# Arduino_MEGA_home_HVAC_v2_0.net
KiCad netlist of a schematic drawn in EAGLE
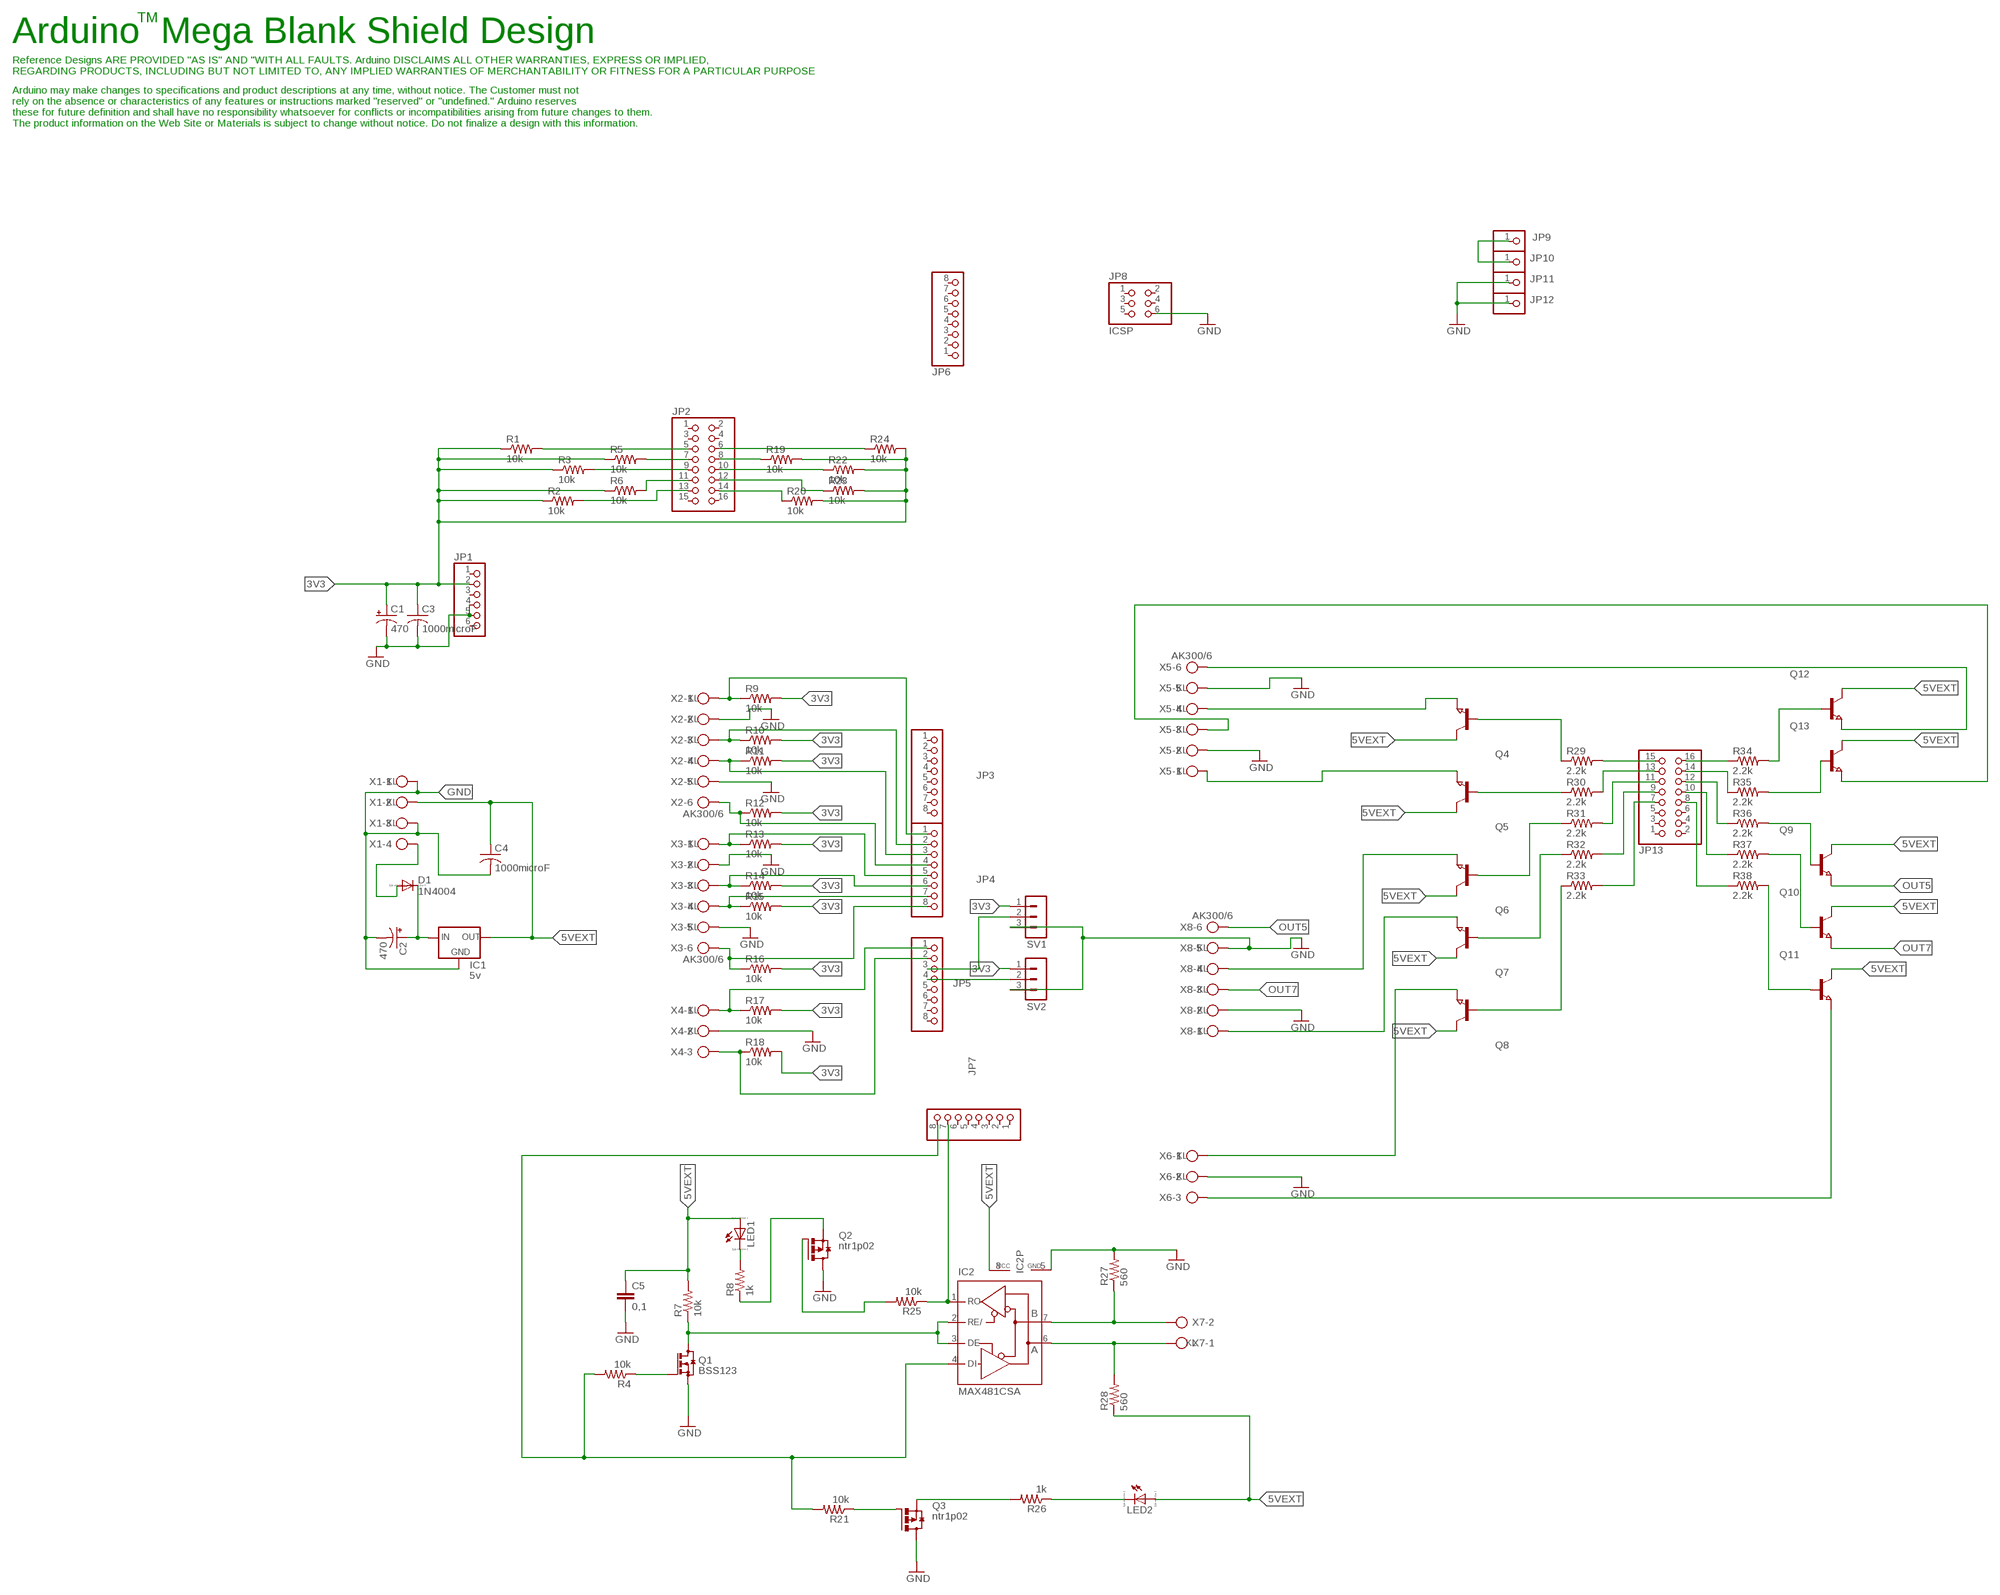
[diagram p0: schematic, sheet 1]

(export (version "E")
  (design (tool "Eeschema 10.0.6"))
  (components
    (comp (ref "C1")
      (value "470")
      (footprint "eagle-import:E5-6")
      (libsource (lib "eagle-import") (part "CPOL-USE5-6"))
    )
    (comp (ref "C2")
      (value "470")
      (footprint "eagle-import:E5-6")
      (libsource (lib "eagle-import") (part "CPOL-USE5-6"))
    )
    (comp (ref "C3")
      (value "1000microF")
      (footprint "eagle-import:C025-040X050")
      (libsource (lib "eagle-import") (part "C-US025-040X050"))
    )
    (comp (ref "C4")
      (value "1000microF")
      (footprint "eagle-import:C025-040X050")
      (libsource (lib "eagle-import") (part "C-US025-040X050"))
    )
    (comp (ref "C5")
      (value "0,1")
      (footprint "eagle-import:C2.5-2")
      (libsource (lib "eagle-import") (part "C2.5/2"))
    )
    (comp (ref "D1")
      (value "1N4004")
      (footprint "eagle-import:DO41-10")
      (libsource (lib "eagle-import") (part "1N4004"))
    )
    (comp (ref "IC1")
      (value "5v")
      (footprint "eagle-import:78MXXL")
      (libsource (lib "eagle-import") (part "78MXXL"))
    )
    (comp (ref "IC2")
      (value "MAX481CSA")
      (footprint "eagle-import:SO08")
      (fields (field (name "MF") "MAXIM"))
      (libsource (lib "eagle-import") (part "MAX481CSA"))
    )
    (comp (ref "JP1")
      (value "PINHD-1X6")
      (footprint "eagle-import:1X06")
      (libsource (lib "eagle-import") (part "PINHD-1X6"))
    )
    (comp (ref "JP2")
      (value "PINHD-2X8")
      (footprint "eagle-import:2X08")
      (libsource (lib "eagle-import") (part "PINHD-2X8"))
    )
    (comp (ref "JP3")
      (value "PINHD-1X8")
      (footprint "eagle-import:1X08")
      (libsource (lib "eagle-import") (part "PINHD-1X8"))
    )
    (comp (ref "JP4")
      (value "PINHD-1X8")
      (footprint "eagle-import:1X08")
      (libsource (lib "eagle-import") (part "PINHD-1X8"))
    )
    (comp (ref "JP5")
      (value "PINHD-1X8")
      (footprint "eagle-import:1X08")
      (libsource (lib "eagle-import") (part "PINHD-1X8"))
    )
    (comp (ref "JP6")
      (value "PINHD-1X8")
      (footprint "eagle-import:1X08")
      (libsource (lib "eagle-import") (part "PINHD-1X8"))
    )
    (comp (ref "JP7")
      (value "PINHD-1X8")
      (footprint "eagle-import:1X08")
      (libsource (lib "eagle-import") (part "PINHD-1X8"))
    )
    (comp (ref "JP8")
      (value "ICSP")
      (footprint "eagle-import:2X03")
      (libsource (lib "eagle-import") (part "PINHD-2X3"))
    )
    (comp (ref "JP9")
      (value "PINHD-1X1")
      (footprint "eagle-import:1X01")
      (libsource (lib "eagle-import") (part "PINHD-1X1"))
    )
    (comp (ref "JP10")
      (value "PINHD-1X1")
      (footprint "eagle-import:1X01")
      (libsource (lib "eagle-import") (part "PINHD-1X1"))
    )
    (comp (ref "JP11")
      (value "PINHD-1X1")
      (footprint "eagle-import:1X01")
      (libsource (lib "eagle-import") (part "PINHD-1X1"))
    )
    (comp (ref "JP12")
      (value "PINHD-1X1")
      (footprint "eagle-import:1X01")
      (libsource (lib "eagle-import") (part "PINHD-1X1"))
    )
    (comp (ref "JP13")
      (value "PINHD-2X8")
      (footprint "eagle-import:2X08")
      (libsource (lib "eagle-import") (part "PINHD-2X8"))
    )
    (comp (ref "LED1")
      (value "LED_E")
      (footprint "eagle-import:LED_1206")
      (libsource (lib "eagle-import") (part "LED_E"))
    )
    (comp (ref "LED2")
      (value "LED_E")
      (footprint "eagle-import:LED_1206")
      (libsource (lib "eagle-import") (part "LED_E"))
    )
    (comp (ref "Q1")
      (value "BSS123")
      (footprint "eagle-import:SOT23")
      (libsource (lib "eagle-import") (part "BSS123"))
    )
    (comp (ref "Q2")
      (value "ntr1p02")
      (footprint "eagle-import:SUPER-SOT3")
      (libsource (lib "eagle-import") (part "FDN360P"))
    )
    (comp (ref "Q3")
      (value "ntr1p02")
      (footprint "eagle-import:SUPER-SOT3")
      (libsource (lib "eagle-import") (part "FDN360P"))
    )
    (comp (ref "Q4")
      (value "NPN-TRANSISTOR_SOT23")
      (footprint "eagle-import:SOT23")
      (libsource (lib "eagle-import") (part "NPN-TRANSISTOR_SOT23"))
    )
    (comp (ref "Q5")
      (value "NPN-TRANSISTOR_SOT23")
      (footprint "eagle-import:SOT23")
      (libsource (lib "eagle-import") (part "NPN-TRANSISTOR_SOT23"))
    )
    (comp (ref "Q6")
      (value "NPN-TRANSISTOR_SOT23")
      (footprint "eagle-import:SOT23")
      (libsource (lib "eagle-import") (part "NPN-TRANSISTOR_SOT23"))
    )
    (comp (ref "Q7")
      (value "NPN-TRANSISTOR_SOT23")
      (footprint "eagle-import:SOT23")
      (libsource (lib "eagle-import") (part "NPN-TRANSISTOR_SOT23"))
    )
    (comp (ref "Q8")
      (value "NPN-TRANSISTOR_SOT23")
      (footprint "eagle-import:SOT23")
      (libsource (lib "eagle-import") (part "NPN-TRANSISTOR_SOT23"))
    )
    (comp (ref "Q9")
      (value "NPN-TRANSISTOR_SOT23")
      (footprint "eagle-import:SOT23")
      (libsource (lib "eagle-import") (part "NPN-TRANSISTOR_SOT23"))
    )
    (comp (ref "Q10")
      (value "NPN-TRANSISTOR_SOT23")
      (footprint "eagle-import:SOT23")
      (libsource (lib "eagle-import") (part "NPN-TRANSISTOR_SOT23"))
    )
    (comp (ref "Q11")
      (value "NPN-TRANSISTOR_SOT23")
      (footprint "eagle-import:SOT23")
      (libsource (lib "eagle-import") (part "NPN-TRANSISTOR_SOT23"))
    )
    (comp (ref "Q12")
      (value "NPN-TRANSISTOR_SOT23")
      (footprint "eagle-import:SOT23")
      (libsource (lib "eagle-import") (part "NPN-TRANSISTOR_SOT23"))
    )
    (comp (ref "Q13")
      (value "NPN-TRANSISTOR_SOT23")
      (footprint "eagle-import:SOT23")
      (libsource (lib "eagle-import") (part "NPN-TRANSISTOR_SOT23"))
    )
    (comp (ref "R1")
      (value "10k")
      (footprint "eagle-import:R0805")
      (libsource (lib "eagle-import") (part "R-US_R0805"))
    )
    (comp (ref "R2")
      (value "10k")
      (footprint "eagle-import:R0805")
      (libsource (lib "eagle-import") (part "R-US_R0805"))
    )
    (comp (ref "R3")
      (value "10k")
      (footprint "eagle-import:R0805")
      (libsource (lib "eagle-import") (part "R-US_R0805"))
    )
    (comp (ref "R4")
      (value "10k")
      (footprint "eagle-import:R0805")
      (libsource (lib "eagle-import") (part "R-US_R0805"))
    )
    (comp (ref "R5")
      (value "10k")
      (footprint "eagle-import:R0805")
      (libsource (lib "eagle-import") (part "R-US_R0805"))
    )
    (comp (ref "R6")
      (value "10k")
      (footprint "eagle-import:R0805")
      (libsource (lib "eagle-import") (part "R-US_R0805"))
    )
    (comp (ref "R7")
      (value "10k")
      (footprint "eagle-import:R0805")
      (libsource (lib "eagle-import") (part "R-US_R0805"))
    )
    (comp (ref "R8")
      (value "1k")
      (footprint "eagle-import:R0805")
      (libsource (lib "eagle-import") (part "R-US_R0805"))
    )
    (comp (ref "R9")
      (value "10k")
      (footprint "eagle-import:R0805")
      (libsource (lib "eagle-import") (part "R-US_R0805"))
    )
    (comp (ref "R10")
      (value "10k")
      (footprint "eagle-import:R0805")
      (libsource (lib "eagle-import") (part "R-US_R0805"))
    )
    (comp (ref "R11")
      (value "10k")
      (footprint "eagle-import:R0805")
      (libsource (lib "eagle-import") (part "R-US_R0805"))
    )
    (comp (ref "R12")
      (value "10k")
      (footprint "eagle-import:R0805")
      (libsource (lib "eagle-import") (part "R-US_R0805"))
    )
    (comp (ref "R13")
      (value "10k")
      (footprint "eagle-import:R0805")
      (libsource (lib "eagle-import") (part "R-US_R0805"))
    )
    (comp (ref "R14")
      (value "10k")
      (footprint "eagle-import:R0805")
      (libsource (lib "eagle-import") (part "R-US_R0805"))
    )
    (comp (ref "R15")
      (value "10k")
      (footprint "eagle-import:R0805")
      (libsource (lib "eagle-import") (part "R-US_R0805"))
    )
    (comp (ref "R16")
      (value "10k")
      (footprint "eagle-import:R0805")
      (libsource (lib "eagle-import") (part "R-US_R0805"))
    )
    (comp (ref "R17")
      (value "10k")
      (footprint "eagle-import:R0805")
      (libsource (lib "eagle-import") (part "R-US_R0805"))
    )
    (comp (ref "R18")
      (value "10k")
      (footprint "eagle-import:R0805")
      (libsource (lib "eagle-import") (part "R-US_R0805"))
    )
    (comp (ref "R19")
      (value "10k")
      (footprint "eagle-import:R0805")
      (libsource (lib "eagle-import") (part "R-US_R0805"))
    )
    (comp (ref "R20")
      (value "10k")
      (footprint "eagle-import:R0805")
      (libsource (lib "eagle-import") (part "R-US_R0805"))
    )
    (comp (ref "R21")
      (value "10k")
      (footprint "eagle-import:R0805")
      (libsource (lib "eagle-import") (part "R-US_R0805"))
    )
    (comp (ref "R22")
      (value "10k")
      (footprint "eagle-import:R0805")
      (libsource (lib "eagle-import") (part "R-US_R0805"))
    )
    (comp (ref "R23")
      (value "10k")
      (footprint "eagle-import:R0805")
      (libsource (lib "eagle-import") (part "R-US_R0805"))
    )
    (comp (ref "R24")
      (value "10k")
      (footprint "eagle-import:R0805")
      (libsource (lib "eagle-import") (part "R-US_R0805"))
    )
    (comp (ref "R25")
      (value "10k")
      (footprint "eagle-import:R0805")
      (libsource (lib "eagle-import") (part "R-US_R0805"))
    )
    (comp (ref "R26")
      (value "1k")
      (footprint "eagle-import:R0805")
      (libsource (lib "eagle-import") (part "R-US_R0805"))
    )
    (comp (ref "R27")
      (value "560")
      (footprint "eagle-import:R0805")
      (libsource (lib "eagle-import") (part "R-US_R0805"))
    )
    (comp (ref "R28")
      (value "560")
      (footprint "eagle-import:R0805")
      (libsource (lib "eagle-import") (part "R-US_R0805"))
    )
    (comp (ref "R29")
      (value "2.2k")
      (footprint "eagle-import:M0805")
      (libsource (lib "eagle-import") (part "R-US_M0805"))
    )
    (comp (ref "R30")
      (value "2.2k")
      (footprint "eagle-import:M0805")
      (libsource (lib "eagle-import") (part "R-US_M0805"))
    )
    (comp (ref "R31")
      (value "2.2k")
      (footprint "eagle-import:M0805")
      (libsource (lib "eagle-import") (part "R-US_M0805"))
    )
    (comp (ref "R32")
      (value "2.2k")
      (footprint "eagle-import:M0805")
      (libsource (lib "eagle-import") (part "R-US_M0805"))
    )
    (comp (ref "R33")
      (value "2.2k")
      (footprint "eagle-import:M0805")
      (libsource (lib "eagle-import") (part "R-US_M0805"))
    )
    (comp (ref "R34")
      (value "2.2k")
      (footprint "eagle-import:M0805")
      (libsource (lib "eagle-import") (part "R-US_M0805"))
    )
    (comp (ref "R35")
      (value "2.2k")
      (footprint "eagle-import:M0805")
      (libsource (lib "eagle-import") (part "R-US_M0805"))
    )
    (comp (ref "R36")
      (value "2.2k")
      (footprint "eagle-import:M0805")
      (libsource (lib "eagle-import") (part "R-US_M0805"))
    )
    (comp (ref "R37")
      (value "2.2k")
      (footprint "eagle-import:M0805")
      (libsource (lib "eagle-import") (part "R-US_M0805"))
    )
    (comp (ref "R38")
      (value "2.2k")
      (footprint "eagle-import:M0805")
      (libsource (lib "eagle-import") (part "R-US_M0805"))
    )
    (comp (ref "SV1")
      (value "MA03-1")
      (footprint "eagle-import:MA03-1")
      (libsource (lib "eagle-import") (part "MA03-1"))
    )
    (comp (ref "SV2")
      (value "MA03-1")
      (footprint "eagle-import:MA03-1")
      (libsource (lib "eagle-import") (part "MA03-1"))
    )
    (comp (ref "X1")
      (value "AK500/4")
      (footprint "eagle-import:AK500_4")
      (libsource (lib "eagle-import") (part "AK500/4"))
    )
    (comp (ref "X2")
      (value "AK300/6")
      (footprint "eagle-import:AK300_6")
      (libsource (lib "eagle-import") (part "AK300/6"))
    )
    (comp (ref "X3")
      (value "AK300/6")
      (footprint "eagle-import:AK300_6")
      (libsource (lib "eagle-import") (part "AK300/6"))
    )
    (comp (ref "X4")
      (value "AK300/3")
      (footprint "eagle-import:AK300_3")
      (libsource (lib "eagle-import") (part "AK300/3"))
    )
    (comp (ref "X5")
      (value "AK300/6")
      (footprint "eagle-import:AK300_6")
      (libsource (lib "eagle-import") (part "AK300/6"))
    )
    (comp (ref "X6")
      (value "AK300/3")
      (footprint "eagle-import:AK300_3")
      (libsource (lib "eagle-import") (part "AK300/3"))
    )
    (comp (ref "X7")
      (value "AK300/2")
      (footprint "eagle-import:AK300_2")
      (libsource (lib "eagle-import") (part "AK300/2"))
    )
    (comp (ref "X8")
      (value "AK300/6")
      (footprint "eagle-import:AK300_6")
      (libsource (lib "eagle-import") (part "AK300/6"))
    )
  )
  (nets
    (net (code "1") (name "3V3") (class "Default")
      (node (ref "C1") (pin "+") (pinfunction "+_+") (pintype "passive"))
      (node (ref "C3") (pin "1") (pinfunction "1_1") (pintype "passive"))
      (node (ref "JP1") (pin "2") (pinfunction "2_2") (pintype "passive"))
      (node (ref "R1") (pin "1") (pinfunction "1_1") (pintype "passive"))
      (node (ref "R10") (pin "2") (pinfunction "2_2") (pintype "passive"))
      (node (ref "R11") (pin "2") (pinfunction "2_2") (pintype "passive"))
      (node (ref "R12") (pin "2") (pinfunction "2_2") (pintype "passive"))
      (node (ref "R13") (pin "2") (pinfunction "2_2") (pintype "passive"))
      (node (ref "R14") (pin "2") (pinfunction "2_2") (pintype "passive"))
      (node (ref "R15") (pin "2") (pinfunction "2_2") (pintype "passive"))
      (node (ref "R16") (pin "2") (pinfunction "2_2") (pintype "passive"))
      (node (ref "R17") (pin "2") (pinfunction "2_2") (pintype "passive"))
      (node (ref "R18") (pin "2") (pinfunction "2_2") (pintype "passive"))
      (node (ref "R19") (pin "2") (pinfunction "2_2") (pintype "passive"))
      (node (ref "R2") (pin "1") (pinfunction "1_1") (pintype "passive"))
      (node (ref "R20") (pin "2") (pinfunction "2_2") (pintype "passive"))
      (node (ref "R22") (pin "2") (pinfunction "2_2") (pintype "passive"))
      (node (ref "R23") (pin "2") (pinfunction "2_2") (pintype "passive"))
      (node (ref "R24") (pin "2") (pinfunction "2_2") (pintype "passive"))
      (node (ref "R3") (pin "1") (pinfunction "1_1") (pintype "passive"))
      (node (ref "R5") (pin "1") (pinfunction "1_1") (pintype "passive"))
      (node (ref "R6") (pin "1") (pinfunction "1_1") (pintype "passive"))
      (node (ref "R9") (pin "2") (pinfunction "2_2") (pintype "passive"))
      (node (ref "SV1") (pin "1") (pinfunction "1_1") (pintype "passive"))
      (node (ref "SV2") (pin "1") (pinfunction "1_1") (pintype "passive"))
    )
    (net (code "2") (name "5VEXT") (class "Default")
      (node (ref "C4") (pin "1") (pinfunction "1_1") (pintype "passive"))
      (node (ref "C5") (pin "1") (pinfunction "1_1") (pintype "passive"))
      (node (ref "IC1") (pin "OUT") (pinfunction "OUT_OUT") (pintype "passive"))
      (node (ref "IC2") (pin "8") (pinfunction "VCC_8") (pintype "power_in"))
      (node (ref "LED1") (pin "A") (pinfunction "A_A") (pintype "passive"))
      (node (ref "LED2") (pin "A") (pinfunction "A_A") (pintype "passive"))
      (node (ref "Q10") (pin "3") (pinfunction "C_3") (pintype "passive"))
      (node (ref "Q11") (pin "3") (pinfunction "C_3") (pintype "passive"))
      (node (ref "Q12") (pin "3") (pinfunction "C_3") (pintype "passive"))
      (node (ref "Q13") (pin "3") (pinfunction "C_3") (pintype "passive"))
      (node (ref "Q4") (pin "3") (pinfunction "C_3") (pintype "passive"))
      (node (ref "Q5") (pin "3") (pinfunction "C_3") (pintype "passive"))
      (node (ref "Q6") (pin "3") (pinfunction "C_3") (pintype "passive"))
      (node (ref "Q7") (pin "3") (pinfunction "C_3") (pintype "passive"))
      (node (ref "Q8") (pin "3") (pinfunction "C_3") (pintype "passive"))
      (node (ref "Q9") (pin "3") (pinfunction "C_3") (pintype "passive"))
      (node (ref "R28") (pin "1") (pinfunction "1_1") (pintype "passive"))
      (node (ref "R7") (pin "2") (pinfunction "2_2") (pintype "passive"))
      (node (ref "X1") (pin "2") (pinfunction "KL_2") (pintype "passive"))
    )
    (net (code "3") (name "GND") (class "Default")
      (node (ref "C1") (pin "-") (pinfunction "-_-") (pintype "passive"))
      (node (ref "C2") (pin "-") (pinfunction "-_-") (pintype "passive"))
      (node (ref "C3") (pin "2") (pinfunction "2_2") (pintype "passive"))
      (node (ref "C4") (pin "2") (pinfunction "2_2") (pintype "passive"))
      (node (ref "C5") (pin "2") (pinfunction "2_2") (pintype "passive"))
      (node (ref "IC1") (pin "GND") (pinfunction "GND_GND") (pintype "input"))
      (node (ref "IC2") (pin "5") (pinfunction "GND_5") (pintype "power_in"))
      (node (ref "JP1") (pin "4") (pinfunction "4_4") (pintype "passive"))
      (node (ref "JP1") (pin "5") (pinfunction "5_5") (pintype "passive"))
      (node (ref "JP11") (pin "1") (pinfunction "1_1") (pintype "passive"))
      (node (ref "JP12") (pin "1") (pinfunction "1_1") (pintype "passive"))
      (node (ref "JP8") (pin "6") (pinfunction "6_6") (pintype "passive"))
      (node (ref "Q1") (pin "2") (pinfunction "S_2") (pintype "passive"))
      (node (ref "Q2") (pin "3") (pinfunction "D_3") (pintype "passive"))
      (node (ref "Q3") (pin "3") (pinfunction "D_3") (pintype "passive"))
      (node (ref "R27") (pin "2") (pinfunction "2_2") (pintype "passive"))
      (node (ref "SV1") (pin "3") (pinfunction "3_3") (pintype "passive"))
      (node (ref "SV2") (pin "3") (pinfunction "3_3") (pintype "passive"))
      (node (ref "X1") (pin "1") (pinfunction "KL_1") (pintype "passive"))
      (node (ref "X1") (pin "3") (pinfunction "KL_3") (pintype "passive"))
      (node (ref "X2") (pin "2") (pinfunction "KL_2") (pintype "passive"))
      (node (ref "X2") (pin "5") (pinfunction "KL_5") (pintype "passive"))
      (node (ref "X3") (pin "2") (pinfunction "KL_2") (pintype "passive"))
      (node (ref "X3") (pin "5") (pinfunction "KL_5") (pintype "passive"))
      (node (ref "X4") (pin "2") (pinfunction "KL_2") (pintype "passive"))
      (node (ref "X5") (pin "2") (pinfunction "KL_2") (pintype "passive"))
      (node (ref "X5") (pin "5") (pinfunction "KL_5") (pintype "passive"))
      (node (ref "X6") (pin "2") (pinfunction "KL_2") (pintype "passive"))
      (node (ref "X8") (pin "2") (pinfunction "KL_2") (pintype "passive"))
      (node (ref "X8") (pin "5") (pinfunction "KL_5") (pintype "passive"))
    )
    (net (code "4") (name "Net-(C2-Pad+)") (class "Default")
      (node (ref "C2") (pin "+") (pinfunction "+_+") (pintype "passive"))
      (node (ref "D1") (pin "C") (pinfunction "C_C") (pintype "passive"))
      (node (ref "IC1") (pin "IN") (pinfunction "IN_IN") (pintype "input"))
    )
    (net (code "5") (name "Net-(IC2A-A)") (class "Default")
      (node (ref "IC2") (pin "6") (pinfunction "A_6") (pintype "passive"))
      (node (ref "R28") (pin "2") (pinfunction "2_2") (pintype "passive"))
      (node (ref "X7") (pin "1") (pinfunction "KL_1") (pintype "passive"))
    )
    (net (code "6") (name "Net-(IC2A-B)") (class "Default")
      (node (ref "IC2") (pin "7") (pinfunction "B_7") (pintype "passive"))
      (node (ref "R27") (pin "1") (pinfunction "1_1") (pintype "passive"))
      (node (ref "X7") (pin "2") (pinfunction "KL_2") (pintype "passive"))
    )
    (net (code "7") (name "Net-(IC2A-DE)") (class "Default")
      (node (ref "IC2") (pin "2") (pinfunction "RE/_2") (pintype "input"))
      (node (ref "IC2") (pin "3") (pinfunction "DE_3") (pintype "input"))
      (node (ref "Q1") (pin "3") (pinfunction "D_3") (pintype "passive"))
      (node (ref "R7") (pin "1") (pinfunction "1_1") (pintype "passive"))
    )
    (net (code "8") (name "Net-(IC2A-DI)") (class "Default")
      (node (ref "IC2") (pin "4") (pinfunction "DI_4") (pintype "input"))
      (node (ref "JP7") (pin "8") (pinfunction "8_8") (pintype "passive"))
      (node (ref "R21") (pin "2") (pinfunction "2_2") (pintype "passive"))
      (node (ref "R4") (pin "2") (pinfunction "2_2") (pintype "passive"))
    )
    (net (code "9") (name "Net-(IC2A-RO)") (class "Default")
      (node (ref "IC2") (pin "1") (pinfunction "RO_1") (pintype "output"))
      (node (ref "JP7") (pin "7") (pinfunction "7_7") (pintype "passive"))
      (node (ref "R25") (pin "1") (pinfunction "1_1") (pintype "passive"))
    )
    (net (code "10") (name "Net-(JP2-Pad5)") (class "Default")
      (node (ref "JP2") (pin "5") (pinfunction "5_5") (pintype "passive"))
      (node (ref "R1") (pin "2") (pinfunction "2_2") (pintype "passive"))
    )
    (net (code "11") (name "Net-(JP2-Pad6)") (class "Default")
      (node (ref "JP2") (pin "6") (pinfunction "6_6") (pintype "passive"))
      (node (ref "R24") (pin "1") (pinfunction "1_1") (pintype "passive"))
    )
    (net (code "12") (name "Net-(JP2-Pad7)") (class "Default")
      (node (ref "JP2") (pin "7") (pinfunction "7_7") (pintype "passive"))
      (node (ref "R5") (pin "2") (pinfunction "2_2") (pintype "passive"))
    )
    (net (code "13") (name "Net-(JP2-Pad8)") (class "Default")
      (node (ref "JP2") (pin "8") (pinfunction "8_8") (pintype "passive"))
      (node (ref "R19") (pin "1") (pinfunction "1_1") (pintype "passive"))
    )
    (net (code "14") (name "Net-(JP2-Pad9)") (class "Default")
      (node (ref "JP2") (pin "9") (pinfunction "9_9") (pintype "passive"))
      (node (ref "R3") (pin "2") (pinfunction "2_2") (pintype "passive"))
    )
    (net (code "15") (name "Net-(JP2-Pad10)") (class "Default")
      (node (ref "JP2") (pin "10") (pinfunction "10_10") (pintype "passive"))
      (node (ref "R22") (pin "1") (pinfunction "1_1") (pintype "passive"))
    )
    (net (code "16") (name "Net-(JP2-Pad11)") (class "Default")
      (node (ref "JP2") (pin "11") (pinfunction "11_11") (pintype "passive"))
      (node (ref "R6") (pin "2") (pinfunction "2_2") (pintype "passive"))
    )
    (net (code "17") (name "Net-(JP2-Pad12)") (class "Default")
      (node (ref "JP2") (pin "12") (pinfunction "12_12") (pintype "passive"))
      (node (ref "R23") (pin "1") (pinfunction "1_1") (pintype "passive"))
    )
    (net (code "18") (name "Net-(JP2-Pad13)") (class "Default")
      (node (ref "JP2") (pin "13") (pinfunction "13_13") (pintype "passive"))
      (node (ref "R2") (pin "2") (pinfunction "2_2") (pintype "passive"))
    )
    (net (code "19") (name "Net-(JP2-Pad14)") (class "Default")
      (node (ref "JP2") (pin "14") (pinfunction "14_14") (pintype "passive"))
      (node (ref "R20") (pin "1") (pinfunction "1_1") (pintype "passive"))
    )
    (net (code "20") (name "Net-(JP5-Pad3)") (class "Default")
      (node (ref "JP5") (pin "3") (pinfunction "3_3") (pintype "passive"))
      (node (ref "SV1") (pin "2") (pinfunction "2_2") (pintype "passive"))
    )
    (net (code "21") (name "Net-(JP5-Pad4)") (class "Default")
      (node (ref "JP5") (pin "4") (pinfunction "4_4") (pintype "passive"))
      (node (ref "SV2") (pin "2") (pinfunction "2_2") (pintype "passive"))
    )
    (net (code "22") (name "Net-(JP10-Pad1)") (class "Default")
      (node (ref "JP10") (pin "1") (pinfunction "1_1") (pintype "passive"))
      (node (ref "JP9") (pin "1") (pinfunction "1_1") (pintype "passive"))
    )
    (net (code "23") (name "Net-(JP13-Pad7)") (class "Default")
      (node (ref "JP13") (pin "7") (pinfunction "7_7") (pintype "passive"))
      (node (ref "R33") (pin "2") (pinfunction "2_2") (pintype "passive"))
    )
    (net (code "24") (name "Net-(JP13-Pad8)") (class "Default")
      (node (ref "JP13") (pin "8") (pinfunction "8_8") (pintype "passive"))
      (node (ref "R38") (pin "1") (pinfunction "1_1") (pintype "passive"))
    )
    (net (code "25") (name "Net-(JP13-Pad9)") (class "Default")
      (node (ref "JP13") (pin "9") (pinfunction "9_9") (pintype "passive"))
      (node (ref "R32") (pin "2") (pinfunction "2_2") (pintype "passive"))
    )
    (net (code "26") (name "Net-(JP13-Pad10)") (class "Default")
      (node (ref "JP13") (pin "10") (pinfunction "10_10") (pintype "passive"))
      (node (ref "R37") (pin "1") (pinfunction "1_1") (pintype "passive"))
    )
    (net (code "27") (name "Net-(JP13-Pad11)") (class "Default")
      (node (ref "JP13") (pin "11") (pinfunction "11_11") (pintype "passive"))
      (node (ref "R31") (pin "2") (pinfunction "2_2") (pintype "passive"))
    )
    (net (code "28") (name "Net-(JP13-Pad12)") (class "Default")
      (node (ref "JP13") (pin "12") (pinfunction "12_12") (pintype "passive"))
      (node (ref "R36") (pin "1") (pinfunction "1_1") (pintype "passive"))
    )
    (net (code "29") (name "Net-(JP13-Pad13)") (class "Default")
      (node (ref "JP13") (pin "13") (pinfunction "13_13") (pintype "passive"))
      (node (ref "R30") (pin "2") (pinfunction "2_2") (pintype "passive"))
    )
    (net (code "30") (name "Net-(JP13-Pad14)") (class "Default")
      (node (ref "JP13") (pin "14") (pinfunction "14_14") (pintype "passive"))
      (node (ref "R35") (pin "1") (pinfunction "1_1") (pintype "passive"))
    )
    (net (code "31") (name "Net-(JP13-Pad15)") (class "Default")
      (node (ref "JP13") (pin "15") (pinfunction "15_15") (pintype "passive"))
      (node (ref "R29") (pin "2") (pinfunction "2_2") (pintype "passive"))
    )
    (net (code "32") (name "Net-(JP13-Pad16)") (class "Default")
      (node (ref "JP13") (pin "16") (pinfunction "16_16") (pintype "passive"))
      (node (ref "R34") (pin "1") (pinfunction "1_1") (pintype "passive"))
    )
    (net (code "33") (name "Net-(LED1-PadC)") (class "Default")
      (node (ref "LED1") (pin "C") (pinfunction "C_C") (pintype "passive"))
      (node (ref "R8") (pin "2") (pinfunction "2_2") (pintype "passive"))
    )
    (net (code "34") (name "Net-(LED2-PadC)") (class "Default")
      (node (ref "LED2") (pin "C") (pinfunction "C_C") (pintype "passive"))
      (node (ref "R26") (pin "1") (pinfunction "1_1") (pintype "passive"))
    )
    (net (code "35") (name "Net-(Q1-G)") (class "Default")
      (node (ref "Q1") (pin "1") (pinfunction "G_1") (pintype "passive"))
      (node (ref "R4") (pin "1") (pinfunction "1_1") (pintype "passive"))
    )
    (net (code "36") (name "Net-(Q2-G)") (class "Default")
      (node (ref "Q2") (pin "1") (pinfunction "G_1") (pintype "passive"))
      (node (ref "R25") (pin "2") (pinfunction "2_2") (pintype "passive"))
    )
    (net (code "37") (name "Net-(Q2-S)") (class "Default")
      (node (ref "Q2") (pin "2") (pinfunction "S_2") (pintype "passive"))
      (node (ref "R8") (pin "1") (pinfunction "1_1") (pintype "passive"))
    )
    (net (code "38") (name "Net-(Q3-G)") (class "Default")
      (node (ref "Q3") (pin "1") (pinfunction "G_1") (pintype "passive"))
      (node (ref "R21") (pin "1") (pinfunction "1_1") (pintype "passive"))
    )
    (net (code "39") (name "Net-(Q3-S)") (class "Default")
      (node (ref "Q3") (pin "2") (pinfunction "S_2") (pintype "passive"))
      (node (ref "R26") (pin "2") (pinfunction "2_2") (pintype "passive"))
    )
    (net (code "40") (name "Net-(Q4-B)") (class "Default")
      (node (ref "Q4") (pin "1") (pinfunction "B_1") (pintype "passive"))
      (node (ref "R29") (pin "1") (pinfunction "1_1") (pintype "passive"))
    )
    (net (code "41") (name "Net-(Q4-E)") (class "Default")
      (node (ref "Q4") (pin "2") (pinfunction "E_2") (pintype "passive"))
      (node (ref "X5") (pin "4") (pinfunction "KL_4") (pintype "passive"))
    )
    (net (code "42") (name "Net-(Q5-B)") (class "Default")
      (node (ref "Q5") (pin "1") (pinfunction "B_1") (pintype "passive"))
      (node (ref "R30") (pin "1") (pinfunction "1_1") (pintype "passive"))
    )
    (net (code "43") (name "Net-(Q5-E)") (class "Default")
      (node (ref "Q5") (pin "2") (pinfunction "E_2") (pintype "passive"))
      (node (ref "X5") (pin "1") (pinfunction "KL_1") (pintype "passive"))
    )
    (net (code "44") (name "Net-(Q6-B)") (class "Default")
      (node (ref "Q6") (pin "1") (pinfunction "B_1") (pintype "passive"))
      (node (ref "R31") (pin "1") (pinfunction "1_1") (pintype "passive"))
    )
    (net (code "45") (name "Net-(Q6-E)") (class "Default")
      (node (ref "Q6") (pin "2") (pinfunction "E_2") (pintype "passive"))
      (node (ref "X8") (pin "4") (pinfunction "KL_4") (pintype "passive"))
    )
    (net (code "46") (name "Net-(Q7-B)") (class "Default")
      (node (ref "Q7") (pin "1") (pinfunction "B_1") (pintype "passive"))
      (node (ref "R32") (pin "1") (pinfunction "1_1") (pintype "passive"))
    )
    (net (code "47") (name "Net-(Q7-E)") (class "Default")
      (node (ref "Q7") (pin "2") (pinfunction "E_2") (pintype "passive"))
      (node (ref "X8") (pin "1") (pinfunction "KL_1") (pintype "passive"))
    )
    (net (code "48") (name "Net-(Q8-B)") (class "Default")
      (node (ref "Q8") (pin "1") (pinfunction "B_1") (pintype "passive"))
      (node (ref "R33") (pin "1") (pinfunction "1_1") (pintype "passive"))
    )
    (net (code "49") (name "Net-(Q8-E)") (class "Default")
      (node (ref "Q8") (pin "2") (pinfunction "E_2") (pintype "passive"))
      (node (ref "X6") (pin "1") (pinfunction "KL_1") (pintype "passive"))
    )
    (net (code "50") (name "Net-(Q9-B)") (class "Default")
      (node (ref "Q9") (pin "1") (pinfunction "B_1") (pintype "passive"))
      (node (ref "R36") (pin "2") (pinfunction "2_2") (pintype "passive"))
    )
    (net (code "51") (name "Net-(Q10-B)") (class "Default")
      (node (ref "Q10") (pin "1") (pinfunction "B_1") (pintype "passive"))
      (node (ref "R37") (pin "2") (pinfunction "2_2") (pintype "passive"))
    )
    (net (code "52") (name "Net-(Q11-B)") (class "Default")
      (node (ref "Q11") (pin "1") (pinfunction "B_1") (pintype "passive"))
      (node (ref "R38") (pin "2") (pinfunction "2_2") (pintype "passive"))
    )
    (net (code "53") (name "Net-(Q11-E)") (class "Default")
      (node (ref "Q11") (pin "2") (pinfunction "E_2") (pintype "passive"))
      (node (ref "X6") (pin "3") (pinfunction "KL_3") (pintype "passive"))
    )
    (net (code "54") (name "Net-(Q12-B)") (class "Default")
      (node (ref "Q12") (pin "1") (pinfunction "B_1") (pintype "passive"))
      (node (ref "R34") (pin "2") (pinfunction "2_2") (pintype "passive"))
    )
    (net (code "55") (name "Net-(Q12-E)") (class "Default")
      (node (ref "Q12") (pin "2") (pinfunction "E_2") (pintype "passive"))
      (node (ref "X5") (pin "6") (pinfunction "KL_6") (pintype "passive"))
    )
    (net (code "56") (name "Net-(Q13-B)") (class "Default")
      (node (ref "Q13") (pin "1") (pinfunction "B_1") (pintype "passive"))
      (node (ref "R35") (pin "2") (pinfunction "2_2") (pintype "passive"))
    )
    (net (code "57") (name "Net-(Q13-E)") (class "Default")
      (node (ref "Q13") (pin "2") (pinfunction "E_2") (pintype "passive"))
      (node (ref "X5") (pin "3") (pinfunction "KL_3") (pintype "passive"))
    )
    (net (code "58") (name "Net-(X1D-KL)") (class "Default")
      (node (ref "D1") (pin "A") (pinfunction "A_A") (pintype "passive"))
      (node (ref "X1") (pin "4") (pinfunction "KL_4") (pintype "passive"))
    )
    (net (code "59") (name "Net-(X2A-KL)") (class "Default")
      (node (ref "JP4") (pin "1") (pinfunction "1_1") (pintype "passive"))
      (node (ref "R9") (pin "1") (pinfunction "1_1") (pintype "passive"))
      (node (ref "X2") (pin "1") (pinfunction "KL_1") (pintype "passive"))
    )
    (net (code "60") (name "Net-(X2C-KL)") (class "Default")
      (node (ref "JP4") (pin "2") (pinfunction "2_2") (pintype "passive"))
      (node (ref "R10") (pin "1") (pinfunction "1_1") (pintype "passive"))
      (node (ref "X2") (pin "3") (pinfunction "KL_3") (pintype "passive"))
    )
    (net (code "61") (name "Net-(X2D-KL)") (class "Default")
      (node (ref "JP4") (pin "3") (pinfunction "3_3") (pintype "passive"))
      (node (ref "R11") (pin "1") (pinfunction "1_1") (pintype "passive"))
      (node (ref "X2") (pin "4") (pinfunction "KL_4") (pintype "passive"))
    )
    (net (code "62") (name "Net-(X2F-KL)") (class "Default")
      (node (ref "JP4") (pin "4") (pinfunction "4_4") (pintype "passive"))
      (node (ref "R12") (pin "1") (pinfunction "1_1") (pintype "passive"))
      (node (ref "X2") (pin "6") (pinfunction "KL_6") (pintype "passive"))
    )
    (net (code "63") (name "Net-(X3A-KL)") (class "Default")
      (node (ref "JP4") (pin "5") (pinfunction "5_5") (pintype "passive"))
      (node (ref "R13") (pin "1") (pinfunction "1_1") (pintype "passive"))
      (node (ref "X3") (pin "1") (pinfunction "KL_1") (pintype "passive"))
    )
    (net (code "64") (name "Net-(X3C-KL)") (class "Default")
      (node (ref "JP4") (pin "6") (pinfunction "6_6") (pintype "passive"))
      (node (ref "R14") (pin "1") (pinfunction "1_1") (pintype "passive"))
      (node (ref "X3") (pin "3") (pinfunction "KL_3") (pintype "passive"))
    )
    (net (code "65") (name "Net-(X3D-KL)") (class "Default")
      (node (ref "JP4") (pin "7") (pinfunction "7_7") (pintype "passive"))
      (node (ref "R15") (pin "1") (pinfunction "1_1") (pintype "passive"))
      (node (ref "X3") (pin "4") (pinfunction "KL_4") (pintype "passive"))
    )
    (net (code "66") (name "Net-(X3F-KL)") (class "Default")
      (node (ref "JP4") (pin "8") (pinfunction "8_8") (pintype "passive"))
      (node (ref "R16") (pin "1") (pinfunction "1_1") (pintype "passive"))
      (node (ref "X3") (pin "6") (pinfunction "KL_6") (pintype "passive"))
    )
    (net (code "67") (name "Net-(X4A-KL)") (class "Default")
      (node (ref "JP5") (pin "1") (pinfunction "1_1") (pintype "passive"))
      (node (ref "R17") (pin "1") (pinfunction "1_1") (pintype "passive"))
      (node (ref "X4") (pin "1") (pinfunction "KL_1") (pintype "passive"))
    )
    (net (code "68") (name "Net-(X4C-KL)") (class "Default")
      (node (ref "JP5") (pin "2") (pinfunction "2_2") (pintype "passive"))
      (node (ref "R18") (pin "1") (pinfunction "1_1") (pintype "passive"))
      (node (ref "X4") (pin "3") (pinfunction "KL_3") (pintype "passive"))
    )
    (net (code "69") (name "OUT5") (class "Default")
      (node (ref "Q9") (pin "2") (pinfunction "E_2") (pintype "passive"))
      (node (ref "X8") (pin "6") (pinfunction "KL_6") (pintype "passive"))
    )
    (net (code "70") (name "OUT7") (class "Default")
      (node (ref "Q10") (pin "2") (pinfunction "E_2") (pintype "passive"))
      (node (ref "X8") (pin "3") (pinfunction "KL_3") (pintype "passive"))
    )
    (net (code "71") (name "unconnected-(JP1-Pad1)") (class "Default")
      (node (ref "JP1") (pin "1") (pinfunction "1_1") (pintype "passive"))
    )
    (net (code "72") (name "unconnected-(JP1-Pad3)") (class "Default")
      (node (ref "JP1") (pin "3") (pinfunction "3_3") (pintype "passive"))
    )
    (net (code "73") (name "unconnected-(JP1-Pad6)") (class "Default")
      (node (ref "JP1") (pin "6") (pinfunction "6_6") (pintype "passive"))
    )
    (net (code "74") (name "unconnected-(JP2-Pad1)") (class "Default")
      (node (ref "JP2") (pin "1") (pinfunction "1_1") (pintype "passive"))
    )
    (net (code "75") (name "unconnected-(JP2-Pad2)") (class "Default")
      (node (ref "JP2") (pin "2") (pinfunction "2_2") (pintype "passive"))
    )
    (net (code "76") (name "unconnected-(JP2-Pad3)") (class "Default")
      (node (ref "JP2") (pin "3") (pinfunction "3_3") (pintype "passive"))
    )
    (net (code "77") (name "unconnected-(JP2-Pad4)") (class "Default")
      (node (ref "JP2") (pin "4") (pinfunction "4_4") (pintype "passive"))
    )
    (net (code "78") (name "unconnected-(JP2-Pad15)") (class "Default")
      (node (ref "JP2") (pin "15") (pinfunction "15_15") (pintype "passive"))
    )
    (net (code "79") (name "unconnected-(JP2-Pad16)") (class "Default")
      (node (ref "JP2") (pin "16") (pinfunction "16_16") (pintype "passive"))
    )
    (net (code "80") (name "unconnected-(JP3-Pad1)") (class "Default")
      (node (ref "JP3") (pin "1") (pinfunction "1_1") (pintype "passive"))
    )
    (net (code "81") (name "unconnected-(JP3-Pad2)") (class "Default")
      (node (ref "JP3") (pin "2") (pinfunction "2_2") (pintype "passive"))
    )
    (net (code "82") (name "unconnected-(JP3-Pad3)") (class "Default")
      (node (ref "JP3") (pin "3") (pinfunction "3_3") (pintype "passive"))
    )
    (net (code "83") (name "unconnected-(JP3-Pad4)") (class "Default")
      (node (ref "JP3") (pin "4") (pinfunction "4_4") (pintype "passive"))
    )
    (net (code "84") (name "unconnected-(JP3-Pad5)") (class "Default")
      (node (ref "JP3") (pin "5") (pinfunction "5_5") (pintype "passive"))
    )
    (net (code "85") (name "unconnected-(JP3-Pad6)") (class "Default")
      (node (ref "JP3") (pin "6") (pinfunction "6_6") (pintype "passive"))
    )
    (net (code "86") (name "unconnected-(JP3-Pad7)") (class "Default")
      (node (ref "JP3") (pin "7") (pinfunction "7_7") (pintype "passive"))
    )
    (net (code "87") (name "unconnected-(JP3-Pad8)") (class "Default")
      (node (ref "JP3") (pin "8") (pinfunction "8_8") (pintype "passive"))
    )
    (net (code "88") (name "unconnected-(JP5-Pad5)") (class "Default")
      (node (ref "JP5") (pin "5") (pinfunction "5_5") (pintype "passive"))
    )
    (net (code "89") (name "unconnected-(JP5-Pad6)") (class "Default")
      (node (ref "JP5") (pin "6") (pinfunction "6_6") (pintype "passive"))
    )
    (net (code "90") (name "unconnected-(JP5-Pad7)") (class "Default")
      (node (ref "JP5") (pin "7") (pinfunction "7_7") (pintype "passive"))
    )
    (net (code "91") (name "unconnected-(JP5-Pad8)") (class "Default")
      (node (ref "JP5") (pin "8") (pinfunction "8_8") (pintype "passive"))
    )
    (net (code "92") (name "unconnected-(JP6-Pad1)") (class "Default")
      (node (ref "JP6") (pin "1") (pinfunction "1_1") (pintype "passive"))
    )
    (net (code "93") (name "unconnected-(JP6-Pad2)") (class "Default")
      (node (ref "JP6") (pin "2") (pinfunction "2_2") (pintype "passive"))
    )
    (net (code "94") (name "unconnected-(JP6-Pad3)") (class "Default")
      (node (ref "JP6") (pin "3") (pinfunction "3_3") (pintype "passive"))
    )
    (net (code "95") (name "unconnected-(JP6-Pad4)") (class "Default")
      (node (ref "JP6") (pin "4") (pinfunction "4_4") (pintype "passive"))
    )
    (net (code "96") (name "unconnected-(JP6-Pad5)") (class "Default")
      (node (ref "JP6") (pin "5") (pinfunction "5_5") (pintype "passive"))
    )
    (net (code "97") (name "unconnected-(JP6-Pad6)") (class "Default")
      (node (ref "JP6") (pin "6") (pinfunction "6_6") (pintype "passive"))
    )
    (net (code "98") (name "unconnected-(JP6-Pad7)") (class "Default")
      (node (ref "JP6") (pin "7") (pinfunction "7_7") (pintype "passive"))
    )
    (net (code "99") (name "unconnected-(JP6-Pad8)") (class "Default")
      (node (ref "JP6") (pin "8") (pinfunction "8_8") (pintype "passive"))
    )
    (net (code "100") (name "unconnected-(JP7-Pad1)") (class "Default")
      (node (ref "JP7") (pin "1") (pinfunction "1_1") (pintype "passive"))
    )
    (net (code "101") (name "unconnected-(JP7-Pad2)") (class "Default")
      (node (ref "JP7") (pin "2") (pinfunction "2_2") (pintype "passive"))
    )
    (net (code "102") (name "unconnected-(JP7-Pad3)") (class "Default")
      (node (ref "JP7") (pin "3") (pinfunction "3_3") (pintype "passive"))
    )
    (net (code "103") (name "unconnected-(JP7-Pad4)") (class "Default")
      (node (ref "JP7") (pin "4") (pinfunction "4_4") (pintype "passive"))
    )
    (net (code "104") (name "unconnected-(JP7-Pad5)") (class "Default")
      (node (ref "JP7") (pin "5") (pinfunction "5_5") (pintype "passive"))
    )
    (net (code "105") (name "unconnected-(JP7-Pad6)") (class "Default")
      (node (ref "JP7") (pin "6") (pinfunction "6_6") (pintype "passive"))
    )
    (net (code "106") (name "unconnected-(JP8-Pad1)") (class "Default")
      (node (ref "JP8") (pin "1") (pinfunction "1_1") (pintype "passive"))
    )
    (net (code "107") (name "unconnected-(JP8-Pad2)") (class "Default")
      (node (ref "JP8") (pin "2") (pinfunction "2_2") (pintype "passive"))
    )
    (net (code "108") (name "unconnected-(JP8-Pad3)") (class "Default")
      (node (ref "JP8") (pin "3") (pinfunction "3_3") (pintype "passive"))
    )
    (net (code "109") (name "unconnected-(JP8-Pad4)") (class "Default")
      (node (ref "JP8") (pin "4") (pinfunction "4_4") (pintype "passive"))
    )
    (net (code "110") (name "unconnected-(JP8-Pad5)") (class "Default")
      (node (ref "JP8") (pin "5") (pinfunction "5_5") (pintype "passive"))
    )
    (net (code "111") (name "unconnected-(JP13-Pad1)") (class "Default")
      (node (ref "JP13") (pin "1") (pinfunction "1_1") (pintype "passive"))
    )
    (net (code "112") (name "unconnected-(JP13-Pad2)") (class "Default")
      (node (ref "JP13") (pin "2") (pinfunction "2_2") (pintype "passive"))
    )
    (net (code "113") (name "unconnected-(JP13-Pad3)") (class "Default")
      (node (ref "JP13") (pin "3") (pinfunction "3_3") (pintype "passive"))
    )
    (net (code "114") (name "unconnected-(JP13-Pad4)") (class "Default")
      (node (ref "JP13") (pin "4") (pinfunction "4_4") (pintype "passive"))
    )
    (net (code "115") (name "unconnected-(JP13-Pad5)") (class "Default")
      (node (ref "JP13") (pin "5") (pinfunction "5_5") (pintype "passive"))
    )
    (net (code "116") (name "unconnected-(JP13-Pad6)") (class "Default")
      (node (ref "JP13") (pin "6") (pinfunction "6_6") (pintype "passive"))
    )
  )
)
